# CH32V467VET-R0.net
KiCad netlist of a schematic drawn in Altium Designer
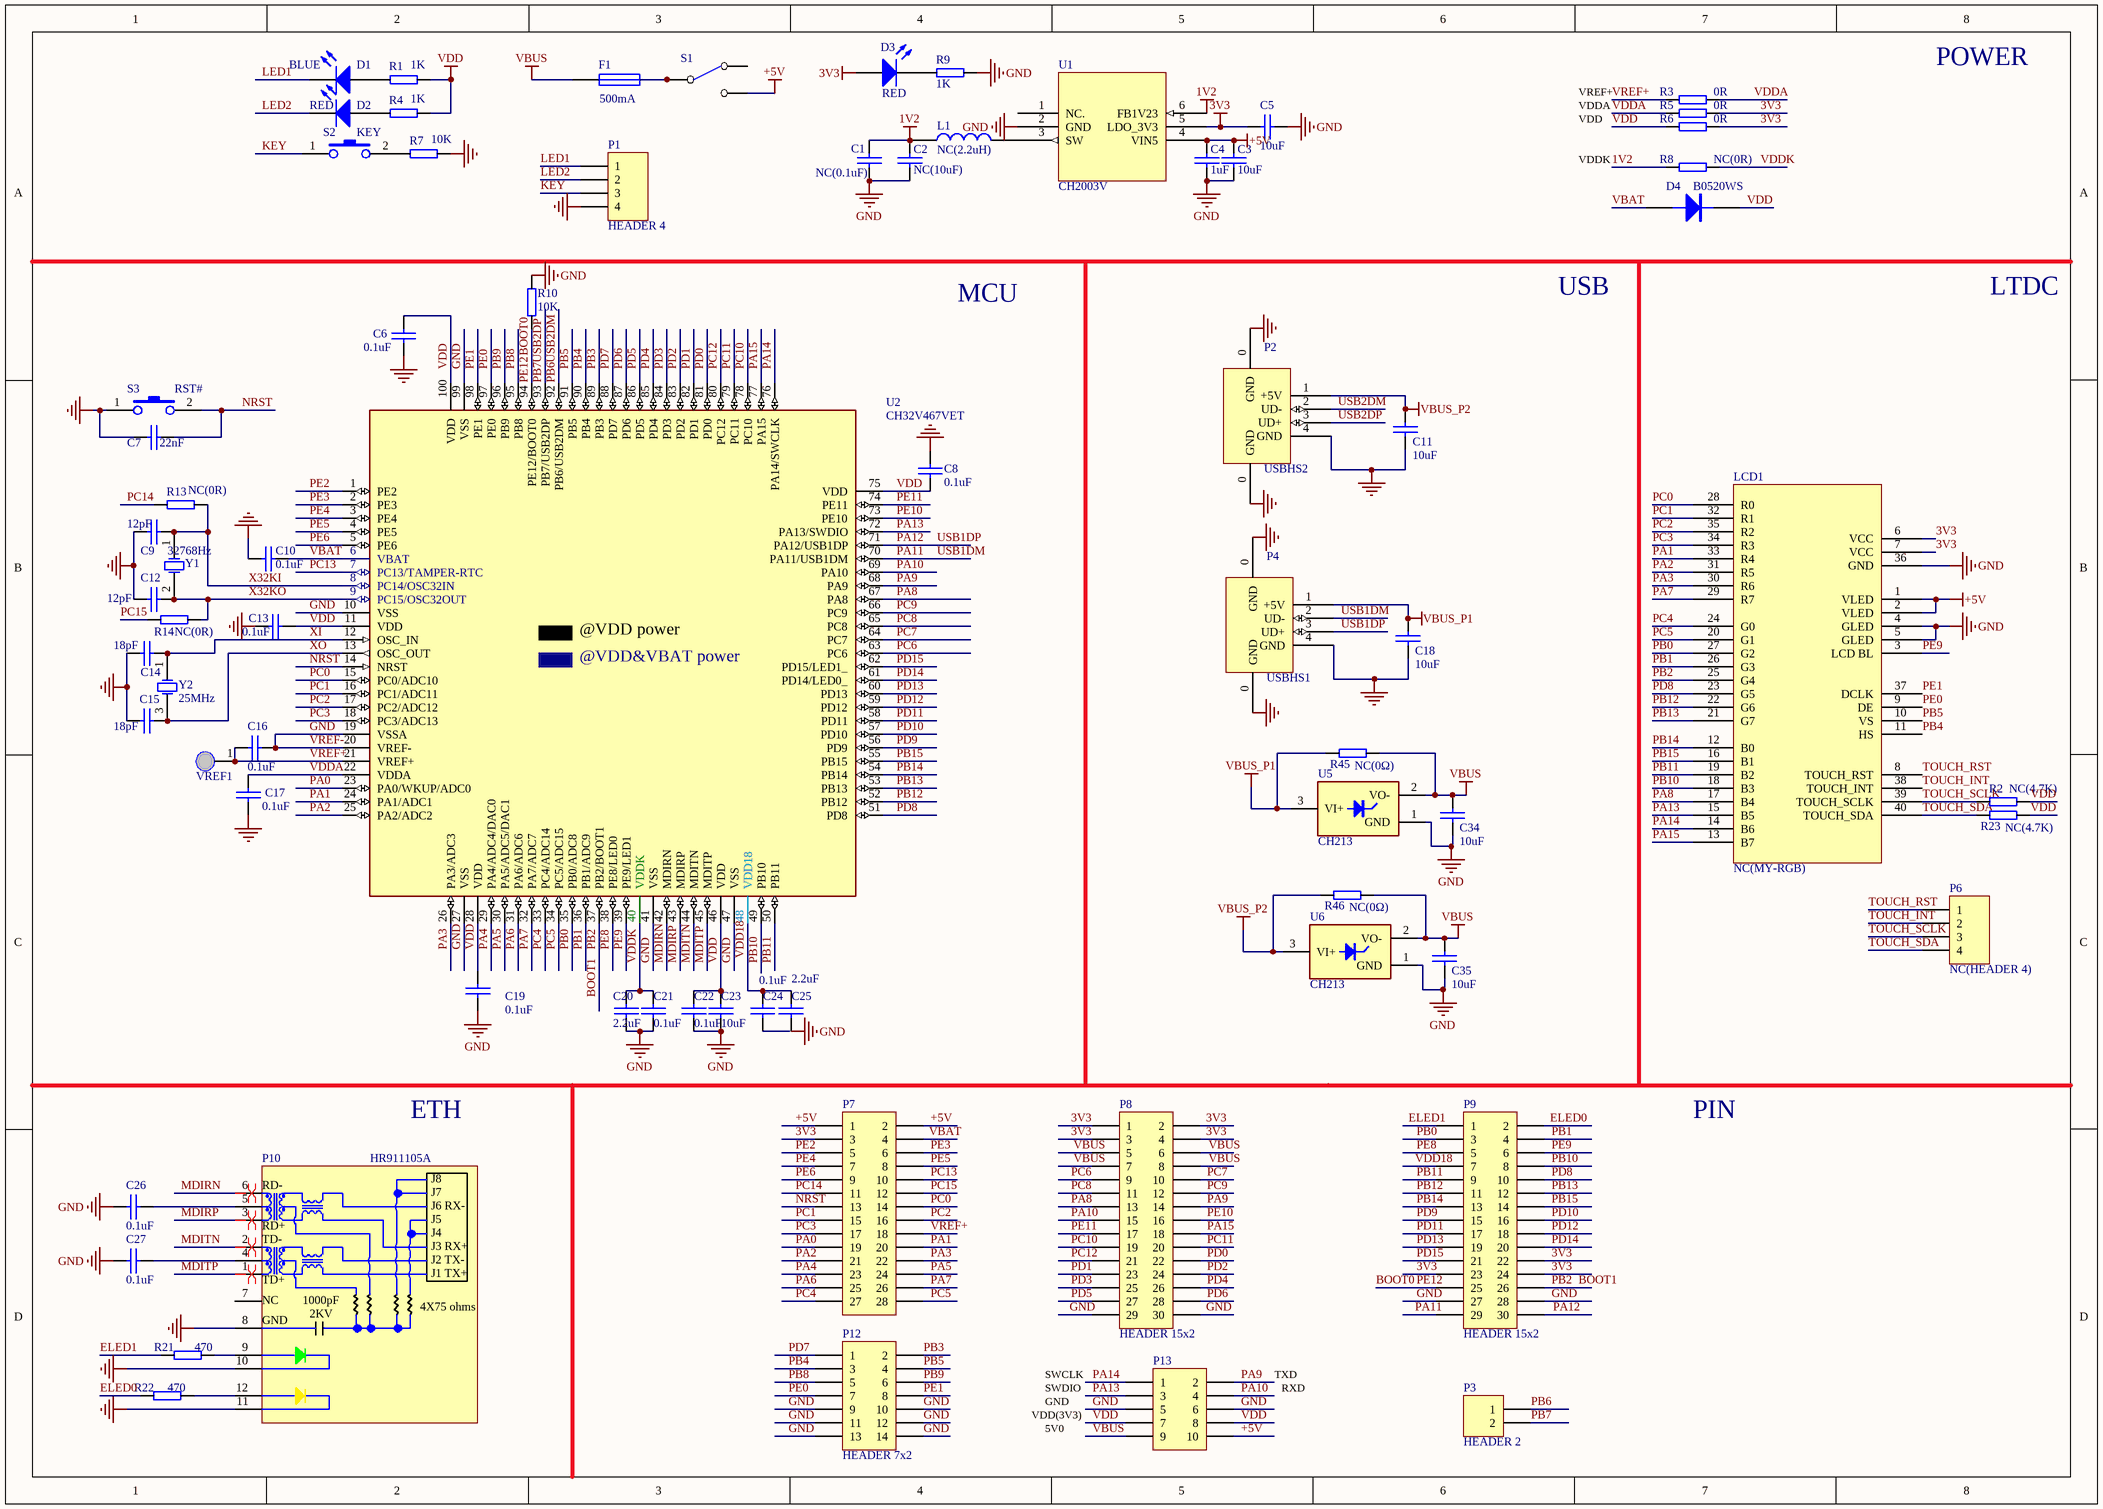
[diagram p0: CH32V467VET-R0.SchDoc]

(export (version "E")
  (design (tool "Eeschema 10.0.6"))
  (components
    (comp (ref "C1")
      (value "NC(0.1uF)")
      (footprint "0402_C")
      (description "Capacitor")
      (libsource (lib "") (part "CAP_2"))
    )
    (comp (ref "C2")
      (value "NC(10uF)")
      (footprint "0603_C")
      (description "Capacitor")
      (libsource (lib "*") (part "CAP"))
    )
    (comp (ref "C3")
      (value "10uF")
      (footprint "0603_C")
      (description "Capacitor")
      (libsource (lib "*") (part "CAP"))
    )
    (comp (ref "C4")
      (value "1uF")
      (footprint "0402_C")
      (description "Capacitor")
      (libsource (lib "") (part "CAP_2"))
    )
    (comp (ref "C5")
      (value "10uF")
      (footprint "0603_C")
      (description "Capacitor")
      (libsource (lib "*") (part "CAP"))
    )
    (comp (ref "C6")
      (value "0.1uF")
      (footprint "0402_C")
      (description "Capacitor")
      (libsource (lib "*") (part "CAP"))
    )
    (comp (ref "C7")
      (value "22nF")
      (footprint "0402_C")
      (description "Capacitor")
      (libsource (lib "") (part "CAP_1"))
    )
    (comp (ref "C8")
      (value "0.1uF")
      (footprint "0402_C")
      (description "Capacitor")
      (libsource (lib "*") (part "CAP"))
    )
    (comp (ref "C9")
      (value "12pF")
      (footprint "0402_C")
      (description "Capacitor")
      (libsource (lib "*") (part "CAP"))
    )
    (comp (ref "C10")
      (value "0.1uF")
      (footprint "0402_C")
      (description "Capacitor")
      (libsource (lib "*") (part "CAP"))
    )
    (comp (ref "C11")
      (value "10uF")
      (footprint "0603_C")
      (description "Capacitor")
      (libsource (lib "") (part "CAP_1"))
    )
    (comp (ref "C12")
      (value "12pF")
      (footprint "0402_C")
      (description "Capacitor")
      (libsource (lib "*") (part "CAP"))
    )
    (comp (ref "C13")
      (value "0.1uF")
      (footprint "0402_C")
      (description "Capacitor")
      (libsource (lib "*") (part "CAP"))
    )
    (comp (ref "C14")
      (value "18pF")
      (footprint "0402_C")
      (description "Capacitor")
      (libsource (lib "*") (part "CAP"))
    )
    (comp (ref "C15")
      (value "18pF")
      (footprint "0402_C")
      (description "Capacitor")
      (libsource (lib "*") (part "CAP"))
    )
    (comp (ref "C16")
      (value "0.1uF")
      (footprint "0402_C")
      (description "Capacitor")
      (libsource (lib "*") (part "CAP"))
    )
    (comp (ref "C17")
      (value "0.1uF")
      (footprint "0402_C")
      (description "Capacitor")
      (libsource (lib "*") (part "CAP"))
    )
    (comp (ref "C18")
      (value "10uF")
      (footprint "0603_C")
      (description "Capacitor")
      (libsource (lib "") (part "CAP_1"))
    )
    (comp (ref "C19")
      (value "0.1uF")
      (footprint "0402_C")
      (description "Capacitor")
      (libsource (lib "*") (part "CAP"))
    )
    (comp (ref "C20")
      (value "2.2uF")
      (footprint "0402_C")
      (description "Capacitor")
      (libsource (lib "*") (part "CAP"))
    )
    (comp (ref "C21")
      (value "0.1uF")
      (footprint "0402_C")
      (description "Capacitor")
      (libsource (lib "*") (part "CAP"))
    )
    (comp (ref "C22")
      (value "0.1uF")
      (footprint "0402_C")
      (description "Capacitor")
      (libsource (lib "*") (part "CAP"))
    )
    (comp (ref "C23")
      (value "10uF")
      (footprint "0402_C")
      (description "Capacitor")
      (libsource (lib "*") (part "CAP"))
    )
    (comp (ref "C24")
      (value "0.1uF")
      (footprint "0402_C")
      (description "Capacitor")
      (libsource (lib "*") (part "CAP"))
    )
    (comp (ref "C25")
      (value "2.2uF")
      (footprint "0402_C")
      (description "Capacitor")
      (libsource (lib "*") (part "CAP"))
    )
    (comp (ref "C26")
      (value "0.1uF")
      (footprint "0402_C")
      (description "Capacitor")
      (libsource (lib "wch_sch_others") (part "CAP"))
    )
    (comp (ref "C27")
      (value "0.1uF")
      (footprint "0402_C")
      (description "Capacitor")
      (libsource (lib "wch_sch_others") (part "CAP"))
    )
    (comp (ref "C34")
      (value "10uF")
      (footprint "0603_C")
      (description "Capacitor")
      (libsource (lib "") (part "CAP_1"))
    )
    (comp (ref "C35")
      (value "10uF")
      (footprint "0603_C")
      (description "Capacitor")
      (libsource (lib "") (part "CAP_1"))
    )
    (comp (ref "D1")
      (value "BLUE")
      (footprint "0603+")
      (description "Typical INFRARED GaAs LED")
      (fields (field (name "PUBLISHER") "Altium Limited"))
      (libsource (lib "*") (part "LED0"))
    )
    (comp (ref "D2")
      (value "RED")
      (footprint "0603+")
      (description "Typical INFRARED GaAs LED")
      (fields (field (name "PUBLISHER") "Altium Limited"))
      (libsource (lib "*") (part "LED0"))
    )
    (comp (ref "D3")
      (value "RED")
      (footprint "0603+")
      (description "Typical INFRARED GaAs LED")
      (fields (field (name "PUBLISHER") "Altium Limited"))
      (libsource (lib "*") (part "LED0"))
    )
    (comp (ref "D4")
      (value "B0520WS")
      (footprint "SOD-323")
      (description "Diode")
      (libsource (lib "*") (part "DIODE"))
    )
    (comp (ref "F1")
      (value "500mA")
      (footprint "0603")
      (description "Fuse")
      (libsource (lib "wch_sch_others") (part "FUSE1"))
    )
    (comp (ref "L1") (value "NC(2.2uH)") (footprint "CD32") (libsource (lib "*") (part "INDUCTOR")))
    (comp (ref "LCD1")
      (value "NC(MY-RGB)")
      (footprint "FPC40P-0.5-FK750M3")
      (libsource (lib "MY-显示") (part "MY-RGB"))
    )
    (comp (ref "P1")
      (value "HEADER 4")
      (footprint "SIP4-2.54mm")
      (description "Header, 4-Pin")
      (libsource (lib "wch_sch_others") (part "HEADER 4"))
    )
    (comp (ref "P2")
      (value "USBHS2")
      (footprint "USBAF")
      (description "USB Port")
      (libsource (lib "*") (part "USB"))
    )
    (comp (ref "P3")
      (value "HEADER 2")
      (footprint "MYPCB:SIP2-2.54mm")
      (description "Header, 2-Pin")
      (libsource (lib "wch_sch_others") (part "HEADER 2"))
    )
    (comp (ref "P4")
      (value "USBHS1")
      (footprint "USBAF")
      (description "USB Port")
      (libsource (lib "*") (part "USB"))
    )
    (comp (ref "P6")
      (value "NC(HEADER 4)")
      (footprint "SIP4-2.54mm")
      (description "Header, 4-Pin")
      (libsource (lib "wch_sch_others") (part "HEADER 4"))
    )
    (comp (ref "P7")
      (value "HEADER 14x2")
      (footprint "MYPCB:IDC28-2.54MM")
      (description "Header, 14-Pin, Dual row")
      (libsource (lib "wch_sch_others") (part "HEADER 14x2"))
    )
    (comp (ref "P8")
      (value "HEADER 15x2")
      (footprint "MYPCB:IDC30-2.54MM")
      (description "Header, 15-Pin, Dual row")
      (libsource (lib "wch_sch_others") (part "HEADER 15x2"))
    )
    (comp (ref "P9")
      (value "HEADER 15x2")
      (footprint "MYPCB:IDC30-2.54MM")
      (description "Header, 15-Pin, Dual row")
      (libsource (lib "wch_sch_others") (part "HEADER 15x2"))
    )
    (comp (ref "P10") (value "HR911105A") (footprint "HR911105A") (libsource (lib "*") (part "HR911105A")))
    (comp (ref "P12")
      (value "HEADER 7x2")
      (footprint "MYPCB:IDC14-2.54mm")
      (description "Header, 7-Pin, Dual row")
      (libsource (lib "wch_sch_others") (part "HEADER 7x2"))
    )
    (comp (ref "P13")
      (value "LINK")
      (footprint "IDC10-2.54mm")
      (description "Header, 5-Pin, Dual row, Right Angle")
      (fields (field (name "PUBLISHER") "Altium Limited"))
      (libsource (lib "Miscellaneous Connectors") (part "Header 5X2H"))
    )
    (comp (ref "R1") (value "1K") (footprint "0402") (libsource (lib "wch_sch_others") (part "RES")))
    (comp (ref "R2") (value "NC(4.7K)") (footprint "0402") (libsource (lib "wch_sch_others") (part "RES")))
    (comp (ref "R3") (value "0R") (footprint "0402") (libsource (lib "*") (part "R")))
    (comp (ref "R4") (value "1K") (footprint "0402") (libsource (lib "wch_sch_others") (part "RES")))
    (comp (ref "R5") (value "0R") (footprint "0402") (libsource (lib "*") (part "R")))
    (comp (ref "R6") (value "0R") (footprint "0402") (libsource (lib "*") (part "R")))
    (comp (ref "R7") (value "10K") (footprint "0402") (libsource (lib "wch_sch_others") (part "RES")))
    (comp (ref "R8") (value "NC(0R)") (footprint "0402") (libsource (lib "*") (part "R")))
    (comp (ref "R9") (value "1K") (footprint "0402") (libsource (lib "wch_sch_others") (part "RES")))
    (comp (ref "R10") (value "10K") (footprint "0402") (libsource (lib "wch_sch_others") (part "RES")))
    (comp (ref "R13") (value "NC(0R)") (footprint "0402") (libsource (lib "wch_sch_others") (part "RES")))
    (comp (ref "R14") (value "NC(0R)") (footprint "0402") (libsource (lib "wch_sch_others") (part "RES")))
    (comp (ref "R21") (value "470") (footprint "0402") (libsource (lib "wch_sch_others") (part "RES")))
    (comp (ref "R22") (value "470") (footprint "0402") (libsource (lib "wch_sch_others") (part "RES")))
    (comp (ref "R23") (value "NC(4.7K)") (footprint "0402") (libsource (lib "wch_sch_others") (part "RES")))
    (comp (ref "R45") (value "NC(0Ω)") (footprint "0402") (libsource (lib "wch_sch_others") (part "RES")))
    (comp (ref "R46") (value "NC(0Ω)") (footprint "0402") (libsource (lib "wch_sch_others") (part "RES")))
    (comp (ref "S1") (value "SW SPDT") (footprint "SW1") (libsource (lib "*") (part "SW SPDT")))
    (comp (ref "S2")
      (value "KEY")
      (footprint "SMD_6.1x3.65x2.5mm-KEY")
      (libsource (lib "wch_sch_others") (part "KEY1"))
    )
    (comp (ref "S3")
      (value "RST#")
      (footprint "SMD_6.1x3.65x2.5mm-KEY")
      (libsource (lib "wch_sch_others") (part "KEY1"))
    )
    (comp (ref "U1")
      (value "CH2003V")
      (footprint "SOT-23-6")
      (description "Step-Down DC-DC Converter, 5V input, 1.23V * 800mA output, with LDO 3.3V * 200mA")
      (libsource (lib "CHXXX") (part "CH2003V"))
    )
    (comp (ref "U2")
      (value "CH32V467VET")
      (footprint "LQFP100")
      (description "RISC-V FPU HD-MCU, 175MHz, USB_480M, 100M Ethernet & Phy, CAN, DVP, ADC, DAC, SRAM")
      (libsource (lib "CHXXX") (part "CH32V467VET"))
    )
    (comp (ref "U5")
      (value "CH213")
      (footprint "SOT-23-3")
      (description "Ideal Diode 5V*1A")
      (libsource (lib "CHXXX") (part "CH213E"))
    )
    (comp (ref "U6")
      (value "CH213")
      (footprint "SOT-23-3")
      (description "Ideal Diode 5V*1A")
      (libsource (lib "CHXXX") (part "CH213E"))
    )
    (comp (ref "VREF1")
      (value "PAD")
      (footprint "TESTPOINT1")
      (description "焊盘")
      (libsource (lib "wch_sch_others") (part "PAD"))
    )
    (comp (ref "Y1")
      (value "32768Hz")
      (footprint "FC-135")
      (description "Crystal Oscillator")
      (fields (field (name "PUBLISHER") "Altium Limited"))
      (libsource (lib "") (part "XTAL_1"))
    )
    (comp (ref "Y2")
      (value "25MHz")
      (footprint "XT3225")
      (description "Crystal Oscillator")
      (fields (field (name "PUBLISHER") "Altium Limited"))
      (libsource (lib "*") (part "XTAL"))
    )
  )
  (nets
    (net (code "1") (name "+5V") (class "Default")
      (node (ref "C3") (pin "2") (pinfunction "2_2") (pintype "passive"))
      (node (ref "C4") (pin "2") (pinfunction "2_2") (pintype "passive"))
      (node (ref "LCD1") (pin "1") (pinfunction "VLED_1") (pintype "passive"))
      (node (ref "LCD1") (pin "2") (pinfunction "VLED_2") (pintype "passive"))
      (node (ref "P13") (pin "10") (pinfunction "10_10") (pintype "passive"))
      (node (ref "P7") (pin "1") (pinfunction "1_1") (pintype "passive"))
      (node (ref "P7") (pin "2") (pinfunction "2_2") (pintype "passive"))
      (node (ref "S1") (pin "2") (pinfunction "NC_2") (pintype "passive"))
      (node (ref "U1") (pin "4") (pinfunction "VIN5_4") (pintype "power_in"))
    )
    (net (code "3") (name "/BOOT0") (class "Default")
      (node (ref "P9") (pin "25") (pinfunction "25_25") (pintype "passive"))
      (node (ref "R10") (pin "2") (pintype "passive"))
      (node (ref "U2") (pin "94") (pinfunction "PE12/BOOT0_94") (pintype "bidirectional"))
    )
    (net (code "4") (name "/BOOT1") (class "Default")
      (node (ref "LCD1") (pin "25") (pinfunction "G4_25") (pintype "passive"))
      (node (ref "P9") (pin "26") (pinfunction "26_26") (pintype "passive"))
      (node (ref "U2") (pin "37") (pinfunction "PB2/BOOT1_37") (pintype "bidirectional"))
    )
    (net (code "5") (name "/ELED0") (class "Default")
      (node (ref "P9") (pin "2") (pinfunction "2_2") (pintype "passive"))
      (node (ref "R22") (pin "1") (pintype "passive"))
    )
    (net (code "6") (name "/ELED1") (class "Default")
      (node (ref "P9") (pin "1") (pinfunction "1_1") (pintype "passive"))
      (node (ref "R21") (pin "1") (pintype "passive"))
    )
    (net (code "7") (name "/KEY") (class "Default")
      (node (ref "P1") (pin "3") (pinfunction "3_3") (pintype "passive"))
      (node (ref "S2") (pin "1") (pinfunction "1_1") (pintype "passive"))
    )
    (net (code "8") (name "/LED1") (class "Default")
      (node (ref "D1") (pin "2") (pinfunction "K_2") (pintype "passive"))
      (node (ref "P1") (pin "1") (pinfunction "1_1") (pintype "passive"))
    )
    (net (code "9") (name "/LED2") (class "Default")
      (node (ref "D2") (pin "2") (pinfunction "K_2") (pintype "passive"))
      (node (ref "P1") (pin "2") (pinfunction "2_2") (pintype "passive"))
    )
    (net (code "10") (name "/MDIRN") (class "Default")
      (node (ref "P10") (pin "6") (pintype "passive"))
      (node (ref "U2") (pin "42") (pinfunction "MDIRN_42") (pintype "bidirectional"))
    )
    (net (code "11") (name "/MDIRP") (class "Default")
      (node (ref "P10") (pin "3") (pintype "passive"))
      (node (ref "U2") (pin "43") (pinfunction "MDIRP_43") (pintype "bidirectional"))
    )
    (net (code "12") (name "/MDITN") (class "Default")
      (node (ref "P10") (pin "2") (pintype "passive"))
      (node (ref "U2") (pin "44") (pinfunction "MDITN_44") (pintype "bidirectional"))
    )
    (net (code "13") (name "/MDITP") (class "Default")
      (node (ref "P10") (pin "1") (pintype "passive"))
      (node (ref "U2") (pin "45") (pinfunction "MDITP_45") (pintype "bidirectional"))
    )
    (net (code "14") (name "/NRST") (class "Default")
      (node (ref "C7") (pin "2") (pinfunction "2_2") (pintype "passive"))
      (node (ref "P7") (pin "13") (pinfunction "13_13") (pintype "passive"))
      (node (ref "S3") (pin "2") (pinfunction "2_2") (pintype "passive"))
      (node (ref "U2") (pin "14") (pinfunction "NRST_14") (pintype "input"))
    )
    (net (code "15") (name "/PA0") (class "Default")
      (node (ref "P7") (pin "19") (pinfunction "19_19") (pintype "passive"))
      (node (ref "U2") (pin "23") (pinfunction "PA0/WKUP/ADC0_23") (pintype "bidirectional"))
    )
    (net (code "16") (name "/PA1") (class "Default")
      (node (ref "LCD1") (pin "33") (pinfunction "R4_33") (pintype "passive"))
      (node (ref "P7") (pin "20") (pinfunction "20_20") (pintype "passive"))
      (node (ref "U2") (pin "24") (pinfunction "PA1/ADC1_24") (pintype "bidirectional"))
    )
    (net (code "17") (name "/PA2") (class "Default")
      (node (ref "LCD1") (pin "31") (pinfunction "R5_31") (pintype "passive"))
      (node (ref "P7") (pin "21") (pinfunction "21_21") (pintype "passive"))
      (node (ref "U2") (pin "25") (pinfunction "PA2/ADC2_25") (pintype "bidirectional"))
    )
    (net (code "18") (name "/PA3") (class "Default")
      (node (ref "LCD1") (pin "30") (pinfunction "R6_30") (pintype "passive"))
      (node (ref "P7") (pin "22") (pinfunction "22_22") (pintype "passive"))
      (node (ref "U2") (pin "26") (pinfunction "PA3/ADC3_26") (pintype "bidirectional"))
    )
    (net (code "19") (name "/PA4") (class "Default")
      (node (ref "P7") (pin "23") (pinfunction "23_23") (pintype "passive"))
      (node (ref "U2") (pin "29") (pinfunction "PA4/ADC4/DAC0_29") (pintype "bidirectional"))
    )
    (net (code "20") (name "/PA5") (class "Default")
      (node (ref "P7") (pin "24") (pinfunction "24_24") (pintype "passive"))
      (node (ref "U2") (pin "30") (pinfunction "PA5/ADC5/DAC1_30") (pintype "bidirectional"))
    )
    (net (code "21") (name "/PA6") (class "Default")
      (node (ref "P7") (pin "25") (pinfunction "25_25") (pintype "passive"))
      (node (ref "U2") (pin "31") (pinfunction "PA6/ADC6_31") (pintype "bidirectional"))
    )
    (net (code "22") (name "/PA7") (class "Default")
      (node (ref "LCD1") (pin "29") (pinfunction "R7_29") (pintype "passive"))
      (node (ref "P7") (pin "26") (pinfunction "26_26") (pintype "passive"))
      (node (ref "U2") (pin "32") (pinfunction "PA7/ADC7_32") (pintype "bidirectional"))
    )
    (net (code "23") (name "/PA8") (class "Default")
      (node (ref "LCD1") (pin "17") (pinfunction "B4_17") (pintype "passive"))
      (node (ref "P8") (pin "13") (pinfunction "13_13") (pintype "passive"))
      (node (ref "U2") (pin "67") (pinfunction "PA8_67") (pintype "bidirectional"))
    )
    (net (code "24") (name "/PA9") (class "Default")
      (node (ref "P13") (pin "2") (pinfunction "2_2") (pintype "passive"))
      (node (ref "P8") (pin "14") (pinfunction "14_14") (pintype "passive"))
      (node (ref "U2") (pin "68") (pinfunction "PA9_68") (pintype "bidirectional"))
    )
    (net (code "25") (name "/PA10") (class "Default")
      (node (ref "P13") (pin "4") (pinfunction "4_4") (pintype "passive"))
      (node (ref "P8") (pin "15") (pinfunction "15_15") (pintype "passive"))
      (node (ref "U2") (pin "69") (pinfunction "PA10_69") (pintype "bidirectional"))
    )
    (net (code "26") (name "/PA11") (class "Default")
      (node (ref "P4") (pin "2") (pinfunction "UD-_2") (pintype "bidirectional"))
      (node (ref "P9") (pin "29") (pinfunction "29_29") (pintype "passive"))
      (node (ref "U2") (pin "70") (pinfunction "PA11/USB1DM_70") (pintype "bidirectional"))
    )
    (net (code "27") (name "/PA12") (class "Default")
      (node (ref "P4") (pin "3") (pinfunction "UD+_3") (pintype "bidirectional"))
      (node (ref "P9") (pin "30") (pinfunction "30_30") (pintype "passive"))
      (node (ref "U2") (pin "71") (pinfunction "PA12/USB1DP_71") (pintype "bidirectional"))
    )
    (net (code "28") (name "/PA13") (class "Default")
      (node (ref "LCD1") (pin "15") (pinfunction "B5_15") (pintype "passive"))
      (node (ref "P13") (pin "3") (pinfunction "3_3") (pintype "passive"))
      (node (ref "U2") (pin "72") (pinfunction "PA13/SWDIO_72") (pintype "bidirectional"))
    )
    (net (code "29") (name "/PA14") (class "Default")
      (node (ref "LCD1") (pin "14") (pinfunction "B6_14") (pintype "passive"))
      (node (ref "P13") (pin "1") (pinfunction "1_1") (pintype "passive"))
      (node (ref "U2") (pin "76") (pinfunction "PA14/SWCLK_76") (pintype "bidirectional"))
    )
    (net (code "30") (name "/PA15") (class "Default")
      (node (ref "LCD1") (pin "13") (pinfunction "B7_13") (pintype "passive"))
      (node (ref "P8") (pin "18") (pinfunction "18_18") (pintype "passive"))
      (node (ref "U2") (pin "77") (pinfunction "PA15_77") (pintype "bidirectional"))
    )
    (net (code "31") (name "/PB0") (class "Default")
      (node (ref "LCD1") (pin "27") (pinfunction "G2_27") (pintype "passive"))
      (node (ref "P9") (pin "3") (pinfunction "3_3") (pintype "passive"))
      (node (ref "U2") (pin "35") (pinfunction "PB0/ADC8_35") (pintype "bidirectional"))
    )
    (net (code "32") (name "/PB1") (class "Default")
      (node (ref "LCD1") (pin "26") (pinfunction "G3_26") (pintype "passive"))
      (node (ref "P9") (pin "4") (pinfunction "4_4") (pintype "passive"))
      (node (ref "U2") (pin "36") (pinfunction "PB1/ADC9_36") (pintype "bidirectional"))
    )
    (net (code "33") (name "/PB3") (class "Default")
      (node (ref "P12") (pin "2") (pinfunction "2_2") (pintype "passive"))
      (node (ref "U2") (pin "89") (pinfunction "PB3_89") (pintype "bidirectional"))
    )
    (net (code "34") (name "/PB4") (class "Default")
      (node (ref "LCD1") (pin "11") (pinfunction "HS_11") (pintype "passive"))
      (node (ref "P12") (pin "3") (pinfunction "3_3") (pintype "passive"))
      (node (ref "U2") (pin "90") (pinfunction "PB4_90") (pintype "bidirectional"))
    )
    (net (code "35") (name "/PB5") (class "Default")
      (node (ref "LCD1") (pin "10") (pinfunction "VS_10") (pintype "passive"))
      (node (ref "P12") (pin "4") (pinfunction "4_4") (pintype "passive"))
      (node (ref "U2") (pin "91") (pinfunction "PB5_91") (pintype "bidirectional"))
    )
    (net (code "36") (name "/PB6") (class "Default")
      (node (ref "P2") (pin "2") (pinfunction "UD-_2") (pintype "bidirectional"))
      (node (ref "P3") (pin "1") (pinfunction "1_1") (pintype "passive"))
      (node (ref "U2") (pin "92") (pinfunction "PB6/USB2DM_92") (pintype "bidirectional"))
    )
    (net (code "37") (name "/PB7") (class "Default")
      (node (ref "P2") (pin "3") (pinfunction "UD+_3") (pintype "bidirectional"))
      (node (ref "P3") (pin "2") (pinfunction "2_2") (pintype "passive"))
      (node (ref "U2") (pin "93") (pinfunction "PB7/USB2DP_93") (pintype "bidirectional"))
    )
    (net (code "38") (name "/PB8") (class "Default")
      (node (ref "P12") (pin "5") (pinfunction "5_5") (pintype "passive"))
      (node (ref "U2") (pin "95") (pinfunction "PB8_95") (pintype "bidirectional"))
    )
    (net (code "39") (name "/PB9") (class "Default")
      (node (ref "P12") (pin "6") (pinfunction "6_6") (pintype "passive"))
      (node (ref "U2") (pin "96") (pinfunction "PB9_96") (pintype "bidirectional"))
    )
    (net (code "40") (name "/PB10") (class "Default")
      (node (ref "LCD1") (pin "18") (pinfunction "B3_18") (pintype "passive"))
      (node (ref "P9") (pin "8") (pinfunction "8_8") (pintype "passive"))
      (node (ref "U2") (pin "49") (pinfunction "PB10_49") (pintype "bidirectional"))
    )
    (net (code "41") (name "/PB11") (class "Default")
      (node (ref "LCD1") (pin "19") (pinfunction "B2_19") (pintype "passive"))
      (node (ref "P9") (pin "9") (pinfunction "9_9") (pintype "passive"))
      (node (ref "U2") (pin "50") (pinfunction "PB11_50") (pintype "bidirectional"))
    )
    (net (code "42") (name "/PB12") (class "Default")
      (node (ref "LCD1") (pin "22") (pinfunction "G6_22") (pintype "passive"))
      (node (ref "P9") (pin "11") (pinfunction "11_11") (pintype "passive"))
      (node (ref "U2") (pin "52") (pinfunction "PB12_52") (pintype "bidirectional"))
    )
    (net (code "43") (name "/PB13") (class "Default")
      (node (ref "LCD1") (pin "21") (pinfunction "G7_21") (pintype "passive"))
      (node (ref "P9") (pin "12") (pinfunction "12_12") (pintype "passive"))
      (node (ref "U2") (pin "53") (pinfunction "PB13_53") (pintype "bidirectional"))
    )
    (net (code "44") (name "/PB14") (class "Default")
      (node (ref "LCD1") (pin "12") (pinfunction "B0_12") (pintype "passive"))
      (node (ref "P9") (pin "13") (pinfunction "13_13") (pintype "passive"))
      (node (ref "U2") (pin "54") (pinfunction "PB14_54") (pintype "bidirectional"))
    )
    (net (code "45") (name "/PB15") (class "Default")
      (node (ref "LCD1") (pin "16") (pinfunction "B1_16") (pintype "passive"))
      (node (ref "P9") (pin "14") (pinfunction "14_14") (pintype "passive"))
      (node (ref "U2") (pin "55") (pinfunction "PB15_55") (pintype "bidirectional"))
    )
    (net (code "46") (name "/PC0") (class "Default")
      (node (ref "LCD1") (pin "28") (pinfunction "R0_28") (pintype "passive"))
      (node (ref "P7") (pin "14") (pinfunction "14_14") (pintype "passive"))
      (node (ref "U2") (pin "15") (pinfunction "PC0/ADC10_15") (pintype "bidirectional"))
    )
    (net (code "47") (name "/PC1") (class "Default")
      (node (ref "LCD1") (pin "32") (pinfunction "R1_32") (pintype "passive"))
      (node (ref "P7") (pin "15") (pinfunction "15_15") (pintype "passive"))
      (node (ref "U2") (pin "16") (pinfunction "PC1/ADC11_16") (pintype "bidirectional"))
    )
    (net (code "48") (name "/PC2") (class "Default")
      (node (ref "LCD1") (pin "35") (pinfunction "R2_35") (pintype "passive"))
      (node (ref "P7") (pin "16") (pinfunction "16_16") (pintype "passive"))
      (node (ref "U2") (pin "17") (pinfunction "PC2/ADC12_17") (pintype "bidirectional"))
    )
    (net (code "49") (name "/PC3") (class "Default")
      (node (ref "LCD1") (pin "34") (pinfunction "R3_34") (pintype "passive"))
      (node (ref "P7") (pin "17") (pinfunction "17_17") (pintype "passive"))
      (node (ref "U2") (pin "18") (pinfunction "PC3/ADC13_18") (pintype "bidirectional"))
    )
    (net (code "50") (name "/PC4") (class "Default")
      (node (ref "LCD1") (pin "24") (pinfunction "G0_24") (pintype "passive"))
      (node (ref "P7") (pin "27") (pinfunction "27_27") (pintype "passive"))
      (node (ref "U2") (pin "33") (pinfunction "PC4/ADC14_33") (pintype "bidirectional"))
    )
    (net (code "51") (name "/PC5") (class "Default")
      (node (ref "LCD1") (pin "20") (pinfunction "G1_20") (pintype "passive"))
      (node (ref "P7") (pin "28") (pinfunction "28_28") (pintype "passive"))
      (node (ref "U2") (pin "34") (pinfunction "PC5/ADC15_34") (pintype "bidirectional"))
    )
    (net (code "52") (name "/PC6") (class "Default")
      (node (ref "P8") (pin "9") (pinfunction "9_9") (pintype "passive"))
      (node (ref "U2") (pin "63") (pinfunction "PC6_63") (pintype "bidirectional"))
    )
    (net (code "53") (name "/PC7") (class "Default")
      (node (ref "P8") (pin "10") (pinfunction "10_10") (pintype "passive"))
      (node (ref "U2") (pin "64") (pinfunction "PC7_64") (pintype "bidirectional"))
    )
    (net (code "54") (name "/PC8") (class "Default")
      (node (ref "P8") (pin "11") (pinfunction "11_11") (pintype "passive"))
      (node (ref "U2") (pin "65") (pinfunction "PC8_65") (pintype "bidirectional"))
    )
    (net (code "55") (name "/PC9") (class "Default")
      (node (ref "P8") (pin "12") (pinfunction "12_12") (pintype "passive"))
      (node (ref "U2") (pin "66") (pinfunction "PC9_66") (pintype "bidirectional"))
    )
    (net (code "56") (name "/PC10") (class "Default")
      (node (ref "P8") (pin "19") (pinfunction "19_19") (pintype "passive"))
      (node (ref "U2") (pin "78") (pinfunction "PC10_78") (pintype "bidirectional"))
    )
    (net (code "57") (name "/PC11") (class "Default")
      (node (ref "P8") (pin "20") (pinfunction "20_20") (pintype "passive"))
      (node (ref "U2") (pin "79") (pinfunction "PC11_79") (pintype "bidirectional"))
    )
    (net (code "58") (name "/PC12") (class "Default")
      (node (ref "P8") (pin "21") (pinfunction "21_21") (pintype "passive"))
      (node (ref "U2") (pin "80") (pinfunction "PC12_80") (pintype "bidirectional"))
    )
    (net (code "59") (name "/PC13") (class "Default")
      (node (ref "P7") (pin "10") (pinfunction "10_10") (pintype "passive"))
      (node (ref "U2") (pin "7") (pinfunction "PC13/TAMPER-RTC_7") (pintype "bidirectional"))
    )
    (net (code "60") (name "/PC14") (class "Default")
      (node (ref "P7") (pin "11") (pinfunction "11_11") (pintype "passive"))
      (node (ref "R13") (pin "1") (pintype "passive"))
    )
    (net (code "61") (name "/PC15") (class "Default")
      (node (ref "P7") (pin "12") (pinfunction "12_12") (pintype "passive"))
      (node (ref "R14") (pin "1") (pintype "passive"))
    )
    (net (code "62") (name "/PD0") (class "Default")
      (node (ref "P8") (pin "22") (pinfunction "22_22") (pintype "passive"))
      (node (ref "U2") (pin "81") (pinfunction "PD0_81") (pintype "bidirectional"))
    )
    (net (code "63") (name "/PD1") (class "Default")
      (node (ref "P8") (pin "23") (pinfunction "23_23") (pintype "passive"))
      (node (ref "U2") (pin "82") (pinfunction "PD1_82") (pintype "bidirectional"))
    )
    (net (code "64") (name "/PD2") (class "Default")
      (node (ref "P8") (pin "24") (pinfunction "24_24") (pintype "passive"))
      (node (ref "U2") (pin "83") (pinfunction "PD2_83") (pintype "bidirectional"))
    )
    (net (code "65") (name "/PD3") (class "Default")
      (node (ref "P8") (pin "25") (pinfunction "25_25") (pintype "passive"))
      (node (ref "U2") (pin "84") (pinfunction "PD3_84") (pintype "bidirectional"))
    )
    (net (code "66") (name "/PD4") (class "Default")
      (node (ref "P8") (pin "26") (pinfunction "26_26") (pintype "passive"))
      (node (ref "U2") (pin "85") (pinfunction "PD4_85") (pintype "bidirectional"))
    )
    (net (code "67") (name "/PD5") (class "Default")
      (node (ref "P8") (pin "27") (pinfunction "27_27") (pintype "passive"))
      (node (ref "U2") (pin "86") (pinfunction "PD5_86") (pintype "bidirectional"))
    )
    (net (code "68") (name "/PD6") (class "Default")
      (node (ref "P8") (pin "28") (pinfunction "28_28") (pintype "passive"))
      (node (ref "U2") (pin "87") (pinfunction "PD6_87") (pintype "bidirectional"))
    )
    (net (code "69") (name "/PD7") (class "Default")
      (node (ref "P12") (pin "1") (pinfunction "1_1") (pintype "passive"))
      (node (ref "U2") (pin "88") (pinfunction "PD7_88") (pintype "bidirectional"))
    )
    (net (code "70") (name "/PD8") (class "Default")
      (node (ref "LCD1") (pin "23") (pinfunction "G5_23") (pintype "passive"))
      (node (ref "P9") (pin "10") (pinfunction "10_10") (pintype "passive"))
      (node (ref "U2") (pin "51") (pinfunction "PD8_51") (pintype "bidirectional"))
    )
    (net (code "71") (name "/PD9") (class "Default")
      (node (ref "P9") (pin "15") (pinfunction "15_15") (pintype "passive"))
      (node (ref "U2") (pin "56") (pinfunction "PD9_56") (pintype "bidirectional"))
    )
    (net (code "72") (name "/PD10") (class "Default")
      (node (ref "P9") (pin "16") (pinfunction "16_16") (pintype "passive"))
      (node (ref "U2") (pin "57") (pinfunction "PD10_57") (pintype "bidirectional"))
    )
    (net (code "73") (name "/PD11") (class "Default")
      (node (ref "P9") (pin "17") (pinfunction "17_17") (pintype "passive"))
      (node (ref "U2") (pin "58") (pinfunction "PD11_58") (pintype "bidirectional"))
    )
    (net (code "74") (name "/PD12") (class "Default")
      (node (ref "P9") (pin "18") (pinfunction "18_18") (pintype "passive"))
      (node (ref "U2") (pin "59") (pinfunction "PD12_59") (pintype "bidirectional"))
    )
    (net (code "75") (name "/PD13") (class "Default")
      (node (ref "P9") (pin "19") (pinfunction "19_19") (pintype "passive"))
      (node (ref "U2") (pin "60") (pinfunction "PD13_60") (pintype "bidirectional"))
    )
    (net (code "76") (name "/PD14") (class "Default")
      (node (ref "P9") (pin "20") (pinfunction "20_20") (pintype "passive"))
      (node (ref "U2") (pin "61") (pinfunction "PD14/LED0__61") (pintype "bidirectional"))
    )
    (net (code "77") (name "/PD15") (class "Default")
      (node (ref "P9") (pin "21") (pinfunction "21_21") (pintype "passive"))
      (node (ref "U2") (pin "62") (pinfunction "PD15/LED1__62") (pintype "bidirectional"))
    )
    (net (code "78") (name "/PE0") (class "Default")
      (node (ref "LCD1") (pin "9") (pinfunction "DE_9") (pintype "passive"))
      (node (ref "P12") (pin "7") (pinfunction "7_7") (pintype "passive"))
      (node (ref "U2") (pin "97") (pinfunction "PE0_97") (pintype "bidirectional"))
    )
    (net (code "79") (name "/PE1") (class "Default")
      (node (ref "LCD1") (pin "37") (pinfunction "DCLK_37") (pintype "passive"))
      (node (ref "P12") (pin "8") (pinfunction "8_8") (pintype "passive"))
      (node (ref "U2") (pin "98") (pinfunction "PE1_98") (pintype "bidirectional"))
    )
    (net (code "80") (name "/PE2") (class "Default")
      (node (ref "P7") (pin "5") (pinfunction "5_5") (pintype "passive"))
      (node (ref "U2") (pin "1") (pinfunction "PE2_1") (pintype "bidirectional"))
    )
    (net (code "81") (name "/PE3") (class "Default")
      (node (ref "P7") (pin "6") (pinfunction "6_6") (pintype "passive"))
      (node (ref "U2") (pin "2") (pinfunction "PE3_2") (pintype "bidirectional"))
    )
    (net (code "82") (name "/PE4") (class "Default")
      (node (ref "P7") (pin "7") (pinfunction "7_7") (pintype "passive"))
      (node (ref "U2") (pin "3") (pinfunction "PE4_3") (pintype "bidirectional"))
    )
    (net (code "83") (name "/PE5") (class "Default")
      (node (ref "P7") (pin "8") (pinfunction "8_8") (pintype "passive"))
      (node (ref "U2") (pin "4") (pinfunction "PE5_4") (pintype "bidirectional"))
    )
    (net (code "84") (name "/PE6") (class "Default")
      (node (ref "P7") (pin "9") (pinfunction "9_9") (pintype "passive"))
      (node (ref "U2") (pin "5") (pinfunction "PE6_5") (pintype "bidirectional"))
    )
    (net (code "85") (name "/PE8") (class "Default")
      (node (ref "P9") (pin "5") (pinfunction "5_5") (pintype "passive"))
      (node (ref "U2") (pin "38") (pinfunction "PE8/LED0_38") (pintype "bidirectional"))
    )
    (net (code "86") (name "/PE9") (class "Default")
      (node (ref "LCD1") (pin "3") (pinfunction "LCD_BL_3") (pintype "passive"))
      (node (ref "P9") (pin "6") (pinfunction "6_6") (pintype "passive"))
      (node (ref "U2") (pin "39") (pinfunction "PE9/LED1_39") (pintype "bidirectional"))
    )
    (net (code "87") (name "/PE10") (class "Default")
      (node (ref "P8") (pin "16") (pinfunction "16_16") (pintype "passive"))
      (node (ref "U2") (pin "73") (pinfunction "PE10_73") (pintype "bidirectional"))
    )
    (net (code "88") (name "/PE11") (class "Default")
      (node (ref "P8") (pin "17") (pinfunction "17_17") (pintype "passive"))
      (node (ref "U2") (pin "74") (pinfunction "PE11_74") (pintype "bidirectional"))
    )
    (net (code "89") (name "/TOUCH_INT") (class "Default")
      (node (ref "LCD1") (pin "38") (pinfunction "TOUCH_INT_38") (pintype "passive"))
      (node (ref "P6") (pin "2") (pinfunction "2_2") (pintype "passive"))
    )
    (net (code "90") (name "/TOUCH_RST") (class "Default")
      (node (ref "LCD1") (pin "8") (pinfunction "TOUCH_RST_8") (pintype "passive"))
      (node (ref "P6") (pin "1") (pinfunction "1_1") (pintype "passive"))
    )
    (net (code "91") (name "/TOUCH_SCLK") (class "Default")
      (node (ref "LCD1") (pin "39") (pinfunction "TOUCH_SCLK_39") (pintype "passive"))
      (node (ref "P6") (pin "3") (pinfunction "3_3") (pintype "passive"))
      (node (ref "R2") (pin "2") (pintype "passive"))
    )
    (net (code "92") (name "/TOUCH_SDA") (class "Default")
      (node (ref "LCD1") (pin "40") (pinfunction "TOUCH_SDA_40") (pintype "passive"))
      (node (ref "P6") (pin "4") (pinfunction "4_4") (pintype "passive"))
      (node (ref "R23") (pin "2") (pintype "passive"))
    )
    (net (code "93") (name "/VBAT") (class "Default")
      (node (ref "C10") (pin "2") (pinfunction "2_2") (pintype "passive"))
      (node (ref "D4") (pin "1") (pinfunction "A_1") (pintype "passive"))
      (node (ref "P7") (pin "4") (pinfunction "4_4") (pintype "passive"))
      (node (ref "U2") (pin "6") (pinfunction "VBAT_6") (pintype "power_in"))
    )
    (net (code "94") (name "/VDD18") (class "Default")
      (node (ref "C24") (pin "2") (pinfunction "2_2") (pintype "passive"))
      (node (ref "C25") (pin "2") (pinfunction "2_2") (pintype "passive"))
      (node (ref "P9") (pin "7") (pinfunction "7_7") (pintype "passive"))
      (node (ref "U2") (pin "48") (pinfunction "VDD18_48") (pintype "power_in"))
    )
    (net (code "95") (name "/VDDA") (class "Default")
      (node (ref "C17") (pin "1") (pinfunction "1_1") (pintype "passive"))
      (node (ref "R3") (pin "1") (pinfunction "1_1") (pintype "passive"))
      (node (ref "R5") (pin "2") (pinfunction "2_2") (pintype "passive"))
      (node (ref "U2") (pin "22") (pinfunction "VDDA_22") (pintype "power_in"))
    )
    (net (code "96") (name "/VDDK") (class "Default")
      (node (ref "C20") (pin "2") (pinfunction "2_2") (pintype "passive"))
      (node (ref "C21") (pin "2") (pinfunction "2_2") (pintype "passive"))
      (node (ref "R8") (pin "1") (pinfunction "1_1") (pintype "passive"))
      (node (ref "U2") (pin "40") (pinfunction "VDDK_40") (pintype "power_in"))
    )
    (net (code "97") (name "/VREF+") (class "Default")
      (node (ref "C16") (pin "1") (pinfunction "1_1") (pintype "passive"))
      (node (ref "P7") (pin "18") (pinfunction "18_18") (pintype "passive"))
      (node (ref "R3") (pin "2") (pinfunction "2_2") (pintype "passive"))
      (node (ref "U2") (pin "21") (pinfunction "VREF+_21") (pintype "power_in"))
      (node (ref "VREF1") (pin "1") (pintype "passive"))
    )
    (net (code "98") (name "/X32KI") (class "Default")
      (node (ref "C9") (pin "2") (pinfunction "2_2") (pintype "passive"))
      (node (ref "R13") (pin "2") (pintype "passive"))
      (node (ref "U2") (pin "8") (pinfunction "PC14/OSC32IN_8") (pintype "bidirectional"))
      (node (ref "Y1") (pin "1") (pinfunction "OSC1_1") (pintype "passive"))
    )
    (net (code "99") (name "/X32KO") (class "Default")
      (node (ref "C12") (pin "2") (pinfunction "2_2") (pintype "passive"))
      (node (ref "R14") (pin "2") (pintype "passive"))
      (node (ref "U2") (pin "9") (pinfunction "PC15/OSC32OUT_9") (pintype "bidirectional"))
      (node (ref "Y1") (pin "2") (pinfunction "OSC2_2") (pintype "passive"))
    )
    (net (code "100") (name "/XI") (class "Default")
      (node (ref "C14") (pin "2") (pinfunction "2_2") (pintype "passive"))
      (node (ref "U2") (pin "12") (pinfunction "OSC_IN_12") (pintype "input"))
      (node (ref "Y2") (pin "1") (pinfunction "OSC1_1") (pintype "passive"))
    )
    (net (code "101") (name "/XO") (class "Default")
      (node (ref "C15") (pin "2") (pinfunction "2_2") (pintype "passive"))
      (node (ref "U2") (pin "13") (pinfunction "OSC_OUT_13") (pintype "output"))
      (node (ref "Y2") (pin "3") (pinfunction "OSC2_3") (pintype "passive"))
    )
    (net (code "102") (name "1V2") (class "Default")
      (node (ref "C1") (pin "2") (pinfunction "2_2") (pintype "passive"))
      (node (ref "C2") (pin "2") (pinfunction "2_2") (pintype "passive"))
      (node (ref "L1") (pin "2") (pinfunction "2_2") (pintype "passive"))
      (node (ref "R8") (pin "2") (pinfunction "2_2") (pintype "passive"))
      (node (ref "U1") (pin "6") (pinfunction "FB1V23_6") (pintype "input"))
    )
    (net (code "103") (name "3V3") (class "Default")
      (node (ref "C5") (pin "2") (pinfunction "2_2") (pintype "passive"))
      (node (ref "D3") (pin "1") (pinfunction "A_1") (pintype "passive"))
      (node (ref "LCD1") (pin "6") (pinfunction "VCC_6") (pintype "passive"))
      (node (ref "LCD1") (pin "7") (pinfunction "VCC_7") (pintype "passive"))
      (node (ref "P7") (pin "3") (pinfunction "3_3") (pintype "passive"))
      (node (ref "P8") (pin "1") (pinfunction "1_1") (pintype "passive"))
      (node (ref "P8") (pin "2") (pinfunction "2_2") (pintype "passive"))
      (node (ref "P8") (pin "3") (pinfunction "3_3") (pintype "passive"))
      (node (ref "P8") (pin "4") (pinfunction "4_4") (pintype "passive"))
      (node (ref "P9") (pin "22") (pinfunction "22_22") (pintype "passive"))
      (node (ref "P9") (pin "23") (pinfunction "23_23") (pintype "passive"))
      (node (ref "P9") (pin "24") (pinfunction "24_24") (pintype "passive"))
      (node (ref "R5") (pin "1") (pinfunction "1_1") (pintype "passive"))
      (node (ref "R6") (pin "1") (pinfunction "1_1") (pintype "passive"))
      (node (ref "U1") (pin "5") (pinfunction "LDO_3V3_5") (pintype "power_in"))
    )
    (net (code "104") (name "GND") (class "Default")
      (node (ref "C1") (pin "1") (pinfunction "1_1") (pintype "passive"))
      (node (ref "C10") (pin "1") (pinfunction "1_1") (pintype "passive"))
      (node (ref "C11") (pin "2") (pinfunction "2_2") (pintype "passive"))
      (node (ref "C12") (pin "1") (pinfunction "1_1") (pintype "passive"))
      (node (ref "C13") (pin "2") (pinfunction "2_2") (pintype "passive"))
      (node (ref "C14") (pin "1") (pinfunction "1_1") (pintype "passive"))
      (node (ref "C15") (pin "1") (pinfunction "1_1") (pintype "passive"))
      (node (ref "C16") (pin "2") (pinfunction "2_2") (pintype "passive"))
      (node (ref "C17") (pin "2") (pinfunction "2_2") (pintype "passive"))
      (node (ref "C18") (pin "2") (pinfunction "2_2") (pintype "passive"))
      (node (ref "C19") (pin "1") (pinfunction "1_1") (pintype "passive"))
      (node (ref "C2") (pin "1") (pinfunction "1_1") (pintype "passive"))
      (node (ref "C20") (pin "1") (pinfunction "1_1") (pintype "passive"))
      (node (ref "C21") (pin "1") (pinfunction "1_1") (pintype "passive"))
      (node (ref "C22") (pin "1") (pinfunction "1_1") (pintype "passive"))
      (node (ref "C23") (pin "1") (pinfunction "1_1") (pintype "passive"))
      (node (ref "C25") (pin "1") (pinfunction "1_1") (pintype "passive"))
      (node (ref "C26") (pin "1") (pinfunction "1_1") (pintype "passive"))
      (node (ref "C27") (pin "1") (pinfunction "1_1") (pintype "passive"))
      (node (ref "C3") (pin "1") (pinfunction "1_1") (pintype "passive"))
      (node (ref "C34") (pin "2") (pinfunction "2_2") (pintype "passive"))
      (node (ref "C35") (pin "2") (pinfunction "2_2") (pintype "passive"))
      (node (ref "C4") (pin "1") (pinfunction "1_1") (pintype "passive"))
      (node (ref "C5") (pin "1") (pinfunction "1_1") (pintype "passive"))
      (node (ref "C6") (pin "1") (pinfunction "1_1") (pintype "passive"))
      (node (ref "C7") (pin "1") (pinfunction "1_1") (pintype "passive"))
      (node (ref "C8") (pin "2") (pinfunction "2_2") (pintype "passive"))
      (node (ref "C9") (pin "1") (pinfunction "1_1") (pintype "passive"))
      (node (ref "LCD1") (pin "36") (pinfunction "GND_36") (pintype "passive"))
      (node (ref "LCD1") (pin "4") (pinfunction "GLED_4") (pintype "passive"))
      (node (ref "LCD1") (pin "5") (pinfunction "GLED_5") (pintype "passive"))
      (node (ref "P1") (pin "4") (pinfunction "4_4") (pintype "passive"))
      (node (ref "P10") (pin "10") (pintype "passive"))
      (node (ref "P10") (pin "11") (pintype "passive"))
      (node (ref "P10") (pin "8") (pintype "passive"))
      (node (ref "P12") (pin "10") (pinfunction "10_10") (pintype "passive"))
      (node (ref "P12") (pin "11") (pinfunction "11_11") (pintype "passive"))
      (node (ref "P12") (pin "12") (pinfunction "12_12") (pintype "passive"))
      (node (ref "P12") (pin "13") (pinfunction "13_13") (pintype "passive"))
      (node (ref "P12") (pin "14") (pinfunction "14_14") (pintype "passive"))
      (node (ref "P12") (pin "9") (pinfunction "9_9") (pintype "passive"))
      (node (ref "P13") (pin "5") (pinfunction "5_5") (pintype "passive"))
      (node (ref "P13") (pin "6") (pinfunction "6_6") (pintype "passive"))
      (node (ref "P2") (pin "0") (pinfunction "GND_0") (pintype "power_in"))
      (node (ref "P2") (pin "4") (pinfunction "GND_4") (pintype "power_in"))
      (node (ref "P4") (pin "0") (pinfunction "GND_0") (pintype "power_in"))
      (node (ref "P4") (pin "4") (pinfunction "GND_4") (pintype "power_in"))
      (node (ref "P8") (pin "29") (pinfunction "29_29") (pintype "passive"))
      (node (ref "P8") (pin "30") (pinfunction "30_30") (pintype "passive"))
      (node (ref "P9") (pin "27") (pinfunction "27_27") (pintype "passive"))
      (node (ref "P9") (pin "28") (pinfunction "28_28") (pintype "passive"))
      (node (ref "R10") (pin "1") (pintype "passive"))
      (node (ref "R7") (pin "1") (pintype "passive"))
      (node (ref "R9") (pin "2") (pintype "passive"))
      (node (ref "S3") (pin "1") (pinfunction "1_1") (pintype "passive"))
      (node (ref "U1") (pin "2") (pinfunction "GND_2") (pintype "power_in"))
      (node (ref "U2") (pin "10") (pinfunction "VSS_10") (pintype "power_in"))
      (node (ref "U2") (pin "19") (pinfunction "VSSA_19") (pintype "power_in"))
      (node (ref "U2") (pin "20") (pinfunction "VREF-_20") (pintype "power_in"))
      (node (ref "U2") (pin "27") (pinfunction "VSS_27") (pintype "power_in"))
      (node (ref "U2") (pin "41") (pinfunction "VSS_41") (pintype "power_in"))
      (node (ref "U2") (pin "47") (pinfunction "VSS_47") (pintype "power_in"))
      (node (ref "U2") (pin "99") (pinfunction "VSS_99") (pintype "power_in"))
      (node (ref "U5") (pin "1") (pinfunction "GND_1") (pintype "power_in"))
      (node (ref "U6") (pin "1") (pinfunction "GND_1") (pintype "power_in"))
    )
    (net (code "105") (name "Net-(C26-Pad2)") (class "Default")
      (node (ref "C26") (pin "2") (pinfunction "2_2") (pintype "passive"))
      (node (ref "P10") (pin "5") (pintype "passive"))
    )
    (net (code "106") (name "Net-(C27-Pad2)") (class "Default")
      (node (ref "C27") (pin "2") (pinfunction "2_2") (pintype "passive"))
      (node (ref "P10") (pin "4") (pintype "passive"))
    )
    (net (code "107") (name "Net-(D1-A)") (class "Default")
      (node (ref "D1") (pin "1") (pinfunction "A_1") (pintype "passive"))
      (node (ref "R1") (pin "2") (pintype "passive"))
    )
    (net (code "108") (name "Net-(D2-A)") (class "Default")
      (node (ref "D2") (pin "1") (pinfunction "A_1") (pintype "passive"))
      (node (ref "R4") (pin "2") (pintype "passive"))
    )
    (net (code "109") (name "Net-(D3-K)") (class "Default")
      (node (ref "D3") (pin "2") (pinfunction "K_2") (pintype "passive"))
      (node (ref "R9") (pin "1") (pintype "passive"))
    )
    (net (code "110") (name "Net-(P10-Pad9)") (class "Default")
      (node (ref "P10") (pin "9") (pintype "passive"))
      (node (ref "R21") (pin "2") (pintype "passive"))
    )
    (net (code "111") (name "Net-(P10-Pad12)") (class "Default")
      (node (ref "P10") (pin "12") (pintype "passive"))
      (node (ref "R22") (pin "2") (pintype "passive"))
    )
    (net (code "112") (name "Net-(R7-Pad2)") (class "Default")
      (node (ref "R7") (pin "2") (pintype "passive"))
      (node (ref "S2") (pin "2") (pinfunction "2_2") (pintype "passive"))
    )
    (net (code "113") (name "Net-(S1-COMMON)") (class "Default")
      (node (ref "F1") (pin "2") (pinfunction "2_2") (pintype "passive"))
      (node (ref "S1") (pin "1") (pinfunction "COMMON_1") (pintype "passive"))
    )
    (net (code "114") (name "Net-(U1-SW)") (class "Default")
      (node (ref "L1") (pin "1") (pinfunction "1_1") (pintype "passive"))
      (node (ref "U1") (pin "3") (pinfunction "SW_3") (pintype "output"))
    )
    (net (code "115") (name "VBUS") (class "Default")
      (node (ref "C34") (pin "1") (pinfunction "1_1") (pintype "passive"))
      (node (ref "C35") (pin "1") (pinfunction "1_1") (pintype "passive"))
      (node (ref "F1") (pin "1") (pinfunction "1_1") (pintype "passive"))
      (node (ref "P13") (pin "9") (pinfunction "9_9") (pintype "passive"))
      (node (ref "P8") (pin "5") (pinfunction "5_5") (pintype "passive"))
      (node (ref "P8") (pin "6") (pinfunction "6_6") (pintype "passive"))
      (node (ref "P8") (pin "7") (pinfunction "7_7") (pintype "passive"))
      (node (ref "P8") (pin "8") (pinfunction "8_8") (pintype "passive"))
      (node (ref "R45") (pin "1") (pintype "passive"))
      (node (ref "R46") (pin "1") (pintype "passive"))
      (node (ref "U5") (pin "2") (pinfunction "VO-_2") (pintype "power_in"))
      (node (ref "U6") (pin "2") (pinfunction "VO-_2") (pintype "power_in"))
    )
    (net (code "116") (name "VBUS_P1") (class "Default")
      (node (ref "C18") (pin "1") (pinfunction "1_1") (pintype "passive"))
      (node (ref "P4") (pin "1") (pinfunction "+5V_1") (pintype "power_in"))
      (node (ref "R45") (pin "2") (pintype "passive"))
      (node (ref "U5") (pin "3") (pinfunction "VI+_3") (pintype "power_in"))
    )
    (net (code "117") (name "VBUS_P2") (class "Default")
      (node (ref "C11") (pin "1") (pinfunction "1_1") (pintype "passive"))
      (node (ref "P2") (pin "1") (pinfunction "+5V_1") (pintype "power_in"))
      (node (ref "R46") (pin "2") (pintype "passive"))
      (node (ref "U6") (pin "3") (pinfunction "VI+_3") (pintype "power_in"))
    )
    (net (code "118") (name "VDD") (class "Default")
      (node (ref "C13") (pin "1") (pinfunction "1_1") (pintype "passive"))
      (node (ref "C19") (pin "2") (pinfunction "2_2") (pintype "passive"))
      (node (ref "C22") (pin "2") (pinfunction "2_2") (pintype "passive"))
      (node (ref "C23") (pin "2") (pinfunction "2_2") (pintype "passive"))
      (node (ref "C6") (pin "2") (pinfunction "2_2") (pintype "passive"))
      (node (ref "C8") (pin "1") (pinfunction "1_1") (pintype "passive"))
      (node (ref "D4") (pin "2") (pinfunction "K_2") (pintype "passive"))
      (node (ref "P13") (pin "7") (pinfunction "7_7") (pintype "passive"))
      (node (ref "P13") (pin "8") (pinfunction "8_8") (pintype "passive"))
      (node (ref "R1") (pin "1") (pintype "passive"))
      (node (ref "R2") (pin "1") (pintype "passive"))
      (node (ref "R23") (pin "1") (pintype "passive"))
      (node (ref "R4") (pin "1") (pintype "passive"))
      (node (ref "R6") (pin "2") (pinfunction "2_2") (pintype "passive"))
      (node (ref "U2") (pin "100") (pinfunction "VDD_100") (pintype "power_in"))
      (node (ref "U2") (pin "11") (pinfunction "VDD_11") (pintype "power_in"))
      (node (ref "U2") (pin "28") (pinfunction "VDD_28") (pintype "power_in"))
      (node (ref "U2") (pin "46") (pinfunction "VDD_46") (pintype "power_in"))
      (node (ref "U2") (pin "75") (pinfunction "VDD_75") (pintype "power_in"))
    )
    (net (code "119") (name "unconnected-(C24-Pad1)") (class "Default")
      (node (ref "C24") (pin "1") (pinfunction "1_1") (pintype "passive"))
    )
    (net (code "120") (name "unconnected-(P10-Pad7)") (class "Default")
      (node (ref "P10") (pin "7") (pintype "passive"))
    )
    (net (code "121") (name "unconnected-(S1-NO-Pad3)") (class "Default")
      (node (ref "S1") (pin "3") (pinfunction "NO_3") (pintype "passive"))
    )
    (net (code "122") (name "unconnected-(U1-NC.-Pad1)") (class "Default")
      (node (ref "U1") (pin "1") (pinfunction "NC._1") (pintype "passive"))
    )
  )
)
